# BUF_input.net
KiCad netlist of a schematic drawn in Altium Designer
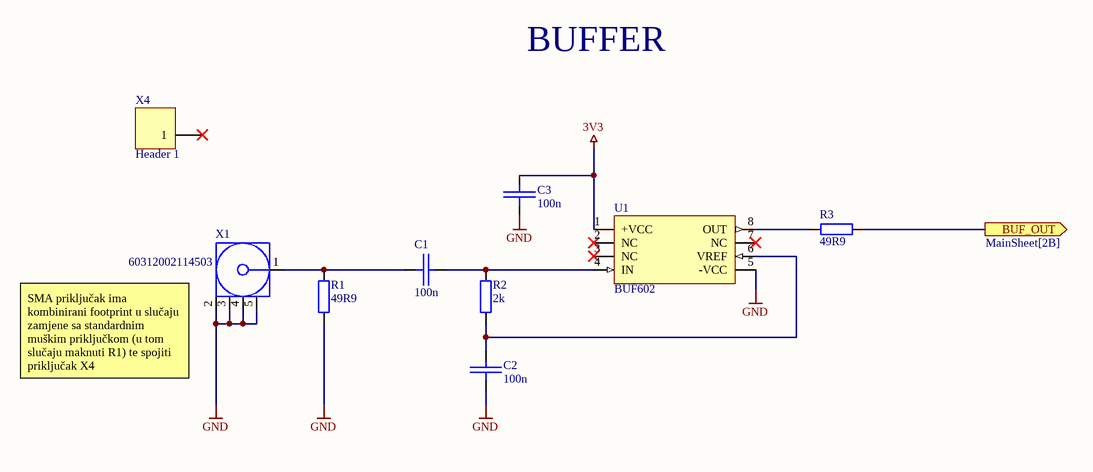
[diagram p0: BUF_input.SchDoc]

(export (version "E")
  (design (tool "Eeschema 10.0.6"))
  (components
    (comp (ref "C1")
      (value "100n")
      (footprint "0805")
      (description "Kondenzator, X7R, 10%, 50VDC")
      (fields
        (field (name "MANUFACTURER") "TDK")
        (field (name "MANUFACTURER PART NUMBER") "C2012X7R1H104K125AE")
      )
      (libsource (lib "DZ1_Bruncic_Vito") (part "MCJCU21GBB7104KTPA01"))
    )
    (comp (ref "C2")
      (value "100n")
      (footprint "0805")
      (description "Kondenzator, X7R, 10%, 50VDC")
      (fields
        (field (name "MANUFACTURER") "TDK")
        (field (name "MANUFACTURER PART NUMBER") "C2012X7R1H104K125AE")
      )
      (libsource (lib "DZ1_Bruncic_Vito") (part "MCJCU21GBB7104KTPA01"))
    )
    (comp (ref "C3")
      (value "100n")
      (footprint "0805")
      (description "Kondenzator, X7R, 10%, 50VDC")
      (fields
        (field (name "MANUFACTURER") "TDK")
        (field (name "MANUFACTURER PART NUMBER") "C2012X7R1H104K125AE")
      )
      (libsource (lib "DZ1_Bruncic_Vito") (part "MCJCU21GBB7104KTPA01"))
    )
    (comp (ref "R1")
      (value "49R9")
      (footprint "0805")
      (description "Otpornik, ±100ppm/C, 125mW")
      (fields
        (field (name "MANUFACTURER") "Yageo")
        (field (name "MANUFACTURER PART NUMBER") "AC0805FR-0749R9L")
      )
      (libsource (lib "DZ1_Bruncic_Vito") (part "AC0805FR-0749R9L"))
    )
    (comp (ref "R2")
      (value "2k")
      (footprint "0805")
      (description "Otpornik, 1%, 125mW")
      (fields
        (field (name "MANUFACTURER") "Yageo")
        (field (name "MANUFACTURER PART NUMBER") "RC0805FR-102KL")
      )
      (libsource (lib "DZ1_Bruncic_Vito") (part "RC0805FR-102KL"))
    )
    (comp (ref "R3")
      (value "49R9")
      (footprint "0805")
      (description "Otpornik, ±100ppm/C, 125mW")
      (fields
        (field (name "MANUFACTURER") "Yageo")
        (field (name "MANUFACTURER PART NUMBER") "AC0805FR-0749R9L")
      )
      (libsource (lib "DZ1_Bruncic_Vito") (part "AC0805FR-0749R9L"))
    )
    (comp (ref "U1")
      (value "BUF602")
      (footprint "SOIC-8")
      (description "Integrirani Buffer")
      (fields
        (field (name "MANUFACTURER") "Texas Instruments")
        (field (name "MANUFACTURER PART NUMBER") "BUF602ID")
      )
      (libsource (lib "DZ1_Bruncic_Vito") (part "BUF602"))
    )
    (comp (ref "X1")
      (value "60312002114503")
      (footprint "SMA")
      (description "SMA priključak")
      (fields (field (name "MANUFACTURER") "Wurth Electronics"))
      (libsource (lib "DZ1_Bruncic_Vito") (part "60312002114503"))
    )
    (comp (ref "X4")
      (value "Header 1")
      (footprint "HDR1X2")
      (description "Header, 1-Pin")
      (fields (field (name "PUBLISHER") "Altium Limited"))
      (libsource (lib "Miscellaneous Connectors") (part "Header 2"))
    )
  )
  (nets
    (net (code "1") (name "/BUF_OUT") (class "Default")
      (node (ref "R3") (pin "2") (pinfunction "2_2") (pintype "passive"))
    )
    (net (code "2") (name "3V3") (class "Default")
      (node (ref "C3") (pin "2") (pinfunction "2_2") (pintype "passive"))
      (node (ref "U1") (pin "1") (pinfunction "+VCC_1") (pintype "power_in"))
    )
    (net (code "3") (name "GND") (class "Default")
      (node (ref "C2") (pin "1") (pinfunction "1_1") (pintype "passive"))
      (node (ref "C3") (pin "1") (pinfunction "1_1") (pintype "passive"))
      (node (ref "R1") (pin "1") (pinfunction "1_1") (pintype "passive"))
      (node (ref "U1") (pin "5") (pinfunction "-VCC_5") (pintype "power_in"))
      (node (ref "X1") (pin "2") (pinfunction "2_2") (pintype "passive"))
      (node (ref "X1") (pin "3") (pinfunction "3_3") (pintype "passive"))
      (node (ref "X1") (pin "4") (pinfunction "4_4") (pintype "passive"))
      (node (ref "X1") (pin "5") (pinfunction "5_5") (pintype "passive"))
    )
    (net (code "4") (name "Net-(C1-Pad1)") (class "Default")
      (node (ref "C1") (pin "1") (pinfunction "1_1") (pintype "passive"))
      (node (ref "R1") (pin "2") (pinfunction "2_2") (pintype "passive"))
      (node (ref "X1") (pin "1") (pinfunction "1_1") (pintype "passive"))
    )
    (net (code "5") (name "Net-(U1-IN)") (class "Default")
      (node (ref "C1") (pin "2") (pinfunction "2_2") (pintype "passive"))
      (node (ref "R2") (pin "2") (pinfunction "2_2") (pintype "passive"))
      (node (ref "U1") (pin "4") (pinfunction "IN_4") (pintype "input"))
    )
    (net (code "6") (name "Net-(U1-OUT)") (class "Default")
      (node (ref "R3") (pin "1") (pinfunction "1_1") (pintype "passive"))
      (node (ref "U1") (pin "8") (pinfunction "OUT_8") (pintype "output"))
    )
    (net (code "7") (name "Net-(U1-VREF)") (class "Default")
      (node (ref "C2") (pin "2") (pinfunction "2_2") (pintype "passive"))
      (node (ref "R2") (pin "1") (pinfunction "1_1") (pintype "passive"))
      (node (ref "U1") (pin "6") (pinfunction "VREF_6") (pintype "input"))
    )
    (net (code "8") (name "unconnected-(U1-NC-Pad2)") (class "Default")
      (node (ref "U1") (pin "2") (pinfunction "NC_2") (pintype "passive+no_connect"))
    )
    (net (code "9") (name "unconnected-(U1-NC-Pad3)") (class "Default")
      (node (ref "U1") (pin "3") (pinfunction "NC_3") (pintype "passive+no_connect"))
    )
    (net (code "10") (name "unconnected-(U1-NC-Pad7)") (class "Default")
      (node (ref "U1") (pin "7") (pinfunction "NC_7") (pintype "passive+no_connect"))
    )
    (net (code "11") (name "unconnected-(X4-Pad1)") (class "Default")
      (node (ref "X4") (pin "1") (pinfunction "1_1") (pintype "passive+no_connect"))
    )
  )
)
